# light_sensor_basic.net
KiCad netlist of a schematic drawn in EAGLE
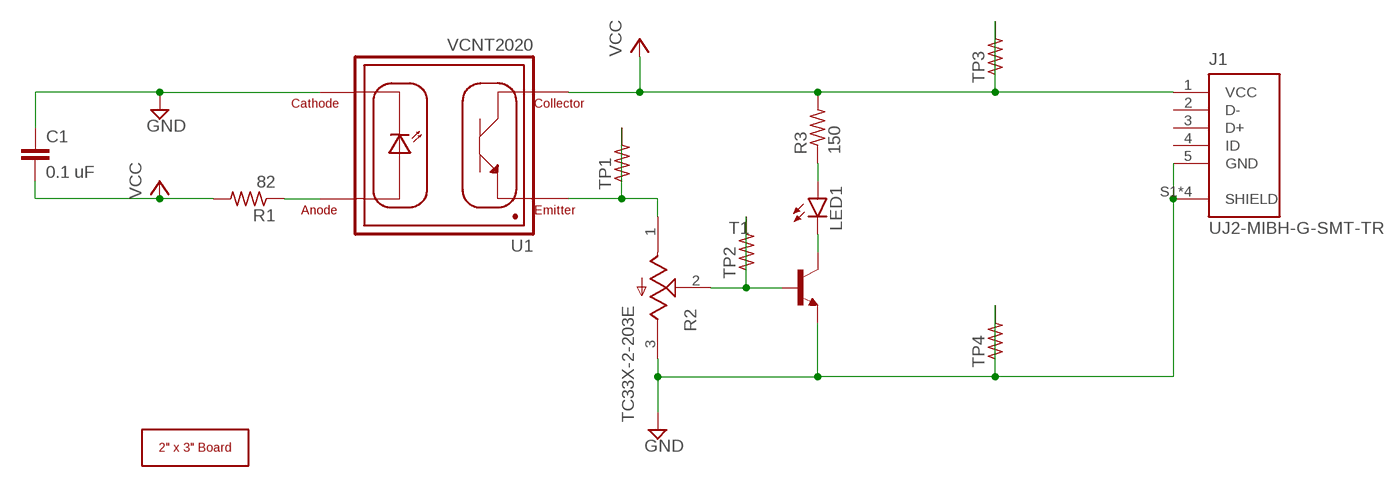
[diagram p0: schematic, sheet 1]

(export (version "E")
  (design (tool "Eeschema 10.0.6"))
  (components
    (comp (ref "C1")
      (value "0.1 uF")
      (footprint "eagle-import:C1206")
      (libsource (lib "eagle-import") (part "C-EUC1206"))
    )
    (comp (ref "J1")
      (value "UJ2-MIBH-G-SMT-TR")
      (footprint "eagle-import:CUI_UJ2-MIBH-G-SMT-TR")
      (fields (field (name "MANUFACTURER") "CUI"))
      (libsource (lib "eagle-import") (part "UJ2-MIBH-G-SMT-TR"))
    )
    (comp (ref "LED1")
      (value "LEDSML0805")
      (footprint "eagle-import:SML0805")
      (libsource (lib "eagle-import") (part "LEDSML0805"))
    )
    (comp (ref "R1")
      (value "82")
      (footprint "eagle-import:R1206")
      (libsource (lib "eagle-import") (part "R-US_R1206"))
    )
    (comp (ref "R2")
      (value "TC33X-2-203E")
      (footprint "eagle-import:TRIM_TC33X-2-203E")
      (fields (field (name "DIGIKEY_PART_NUMBER") "TC33X-2-203ETR-ND") (field (name "MF") "Bourns"))
      (libsource (lib "eagle-import") (part "TC33X-2-203E"))
    )
    (comp (ref "R3")
      (value "150")
      (footprint "eagle-import:R0805")
      (libsource (lib "eagle-import") (part "R-US_R0805"))
    )
    (comp (ref "T1")
      (value "-NPN-SOT23-EBC")
      (footprint "eagle-import:SOT23-EBC")
      (libsource (lib "eagle-import") (part "-NPN-SOT23-EBC"))
    )
    (comp (ref "TP1")
      (value "R-US_R1206")
      (footprint "eagle-import:R1206")
      (libsource (lib "eagle-import") (part "R-US_R1206"))
    )
    (comp (ref "TP2")
      (value "R-US_R1206")
      (footprint "eagle-import:R1206")
      (libsource (lib "eagle-import") (part "R-US_R1206"))
    )
    (comp (ref "TP3")
      (value "R-US_R1206")
      (footprint "eagle-import:R1206")
      (libsource (lib "eagle-import") (part "R-US_R1206"))
    )
    (comp (ref "TP4")
      (value "R-US_R1206")
      (footprint "eagle-import:R1206")
      (libsource (lib "eagle-import") (part "R-US_R1206"))
    )
    (comp (ref "U$1")
      (value "2X3_BOARD_V2")
      (footprint "eagle-import:2X3_BOARD_V2")
      (libsource (lib "eagle-import") (part "2X3_BOARD_V2"))
    )
    (comp (ref "U1")
      (value "VCNT2020")
      (footprint "eagle-import:XDCR_VCNT2020")
      (fields (field (name "DIGIKEY_PART_NUMBER") "VCNT2020TR-ND") (field (name "MF") "Vishay"))
      (libsource (lib "eagle-import") (part "VCNT2020"))
    )
  )
  (nets
    (net (code "1") (name "GND") (class "Default")
      (node (ref "C1") (pin "1") (pinfunction "1_1") (pintype "passive"))
      (node (ref "J1") (pin "5") (pinfunction "GND_5") (pintype "power_in"))
      (node (ref "J1") (pin "S1") (pinfunction "SHIELD_S1") (pintype "passive"))
      (node (ref "J1") (pin "S2") (pinfunction "SHIELD_S2") (pintype "passive"))
      (node (ref "J1") (pin "S3") (pinfunction "SHIELD_S3") (pintype "passive"))
      (node (ref "J1") (pin "S4") (pinfunction "SHIELD_S4") (pintype "passive"))
      (node (ref "R2") (pin "3") (pinfunction "CW_3") (pintype "passive"))
      (node (ref "T1") (pin "E") (pinfunction "E_E") (pintype "passive"))
      (node (ref "TP4") (pin "1") (pinfunction "1_1") (pintype "passive"))
      (node (ref "TP4") (pin "2") (pinfunction "2_2") (pintype "passive"))
      (node (ref "U1") (pin "4") (pinfunction "CATHODE_4") (pintype "passive"))
    )
    (net (code "2") (name "Net-(LED1-PadA)") (class "Default")
      (node (ref "LED1") (pin "A") (pinfunction "A_A") (pintype "passive"))
      (node (ref "R3") (pin "1") (pinfunction "1_1") (pintype "passive"))
    )
    (net (code "3") (name "Net-(LED1-PadC)") (class "Default")
      (node (ref "LED1") (pin "C") (pinfunction "C_C") (pintype "passive"))
      (node (ref "T1") (pin "C") (pinfunction "C_C") (pintype "passive"))
    )
    (net (code "4") (name "Net-(R2-CCW)") (class "Default")
      (node (ref "R2") (pin "1") (pinfunction "CCW_1") (pintype "passive"))
      (node (ref "TP1") (pin "1") (pinfunction "1_1") (pintype "passive"))
      (node (ref "TP1") (pin "2") (pinfunction "2_2") (pintype "passive"))
      (node (ref "U1") (pin "1") (pinfunction "EMITTER_1") (pintype "passive"))
    )
    (net (code "5") (name "Net-(R2-W)") (class "Default")
      (node (ref "R2") (pin "2") (pinfunction "W_2") (pintype "passive"))
      (node (ref "T1") (pin "B") (pinfunction "B_B") (pintype "passive"))
      (node (ref "TP2") (pin "1") (pinfunction "1_1") (pintype "passive"))
      (node (ref "TP2") (pin "2") (pinfunction "2_2") (pintype "passive"))
    )
    (net (code "6") (name "Net-(U1-ANODE)") (class "Default")
      (node (ref "R1") (pin "1") (pinfunction "1_1") (pintype "passive"))
      (node (ref "U1") (pin "3") (pinfunction "ANODE_3") (pintype "passive"))
    )
    (net (code "7") (name "VCC") (class "Default")
      (node (ref "C1") (pin "2") (pinfunction "2_2") (pintype "passive"))
      (node (ref "J1") (pin "1") (pinfunction "VCC_1") (pintype "power_in"))
      (node (ref "R1") (pin "2") (pinfunction "2_2") (pintype "passive"))
      (node (ref "R3") (pin "2") (pinfunction "2_2") (pintype "passive"))
      (node (ref "TP3") (pin "1") (pinfunction "1_1") (pintype "passive"))
      (node (ref "TP3") (pin "2") (pinfunction "2_2") (pintype "passive"))
      (node (ref "U1") (pin "2") (pinfunction "COLLECTOR_2") (pintype "passive"))
    )
    (net (code "8") (name "unconnected-(J1-D+-Pad3)") (class "Default")
      (node (ref "J1") (pin "3") (pinfunction "D+_3") (pintype "bidirectional"))
    )
    (net (code "9") (name "unconnected-(J1-D--Pad2)") (class "Default")
      (node (ref "J1") (pin "2") (pinfunction "D-_2") (pintype "bidirectional"))
    )
    (net (code "10") (name "unconnected-(J1-ID-Pad4)") (class "Default")
      (node (ref "J1") (pin "4") (pinfunction "ID_4") (pintype "bidirectional"))
    )
  )
)
